# con-bot-j1-1.net
KiCad netlist of a schematic drawn in Altium Designer
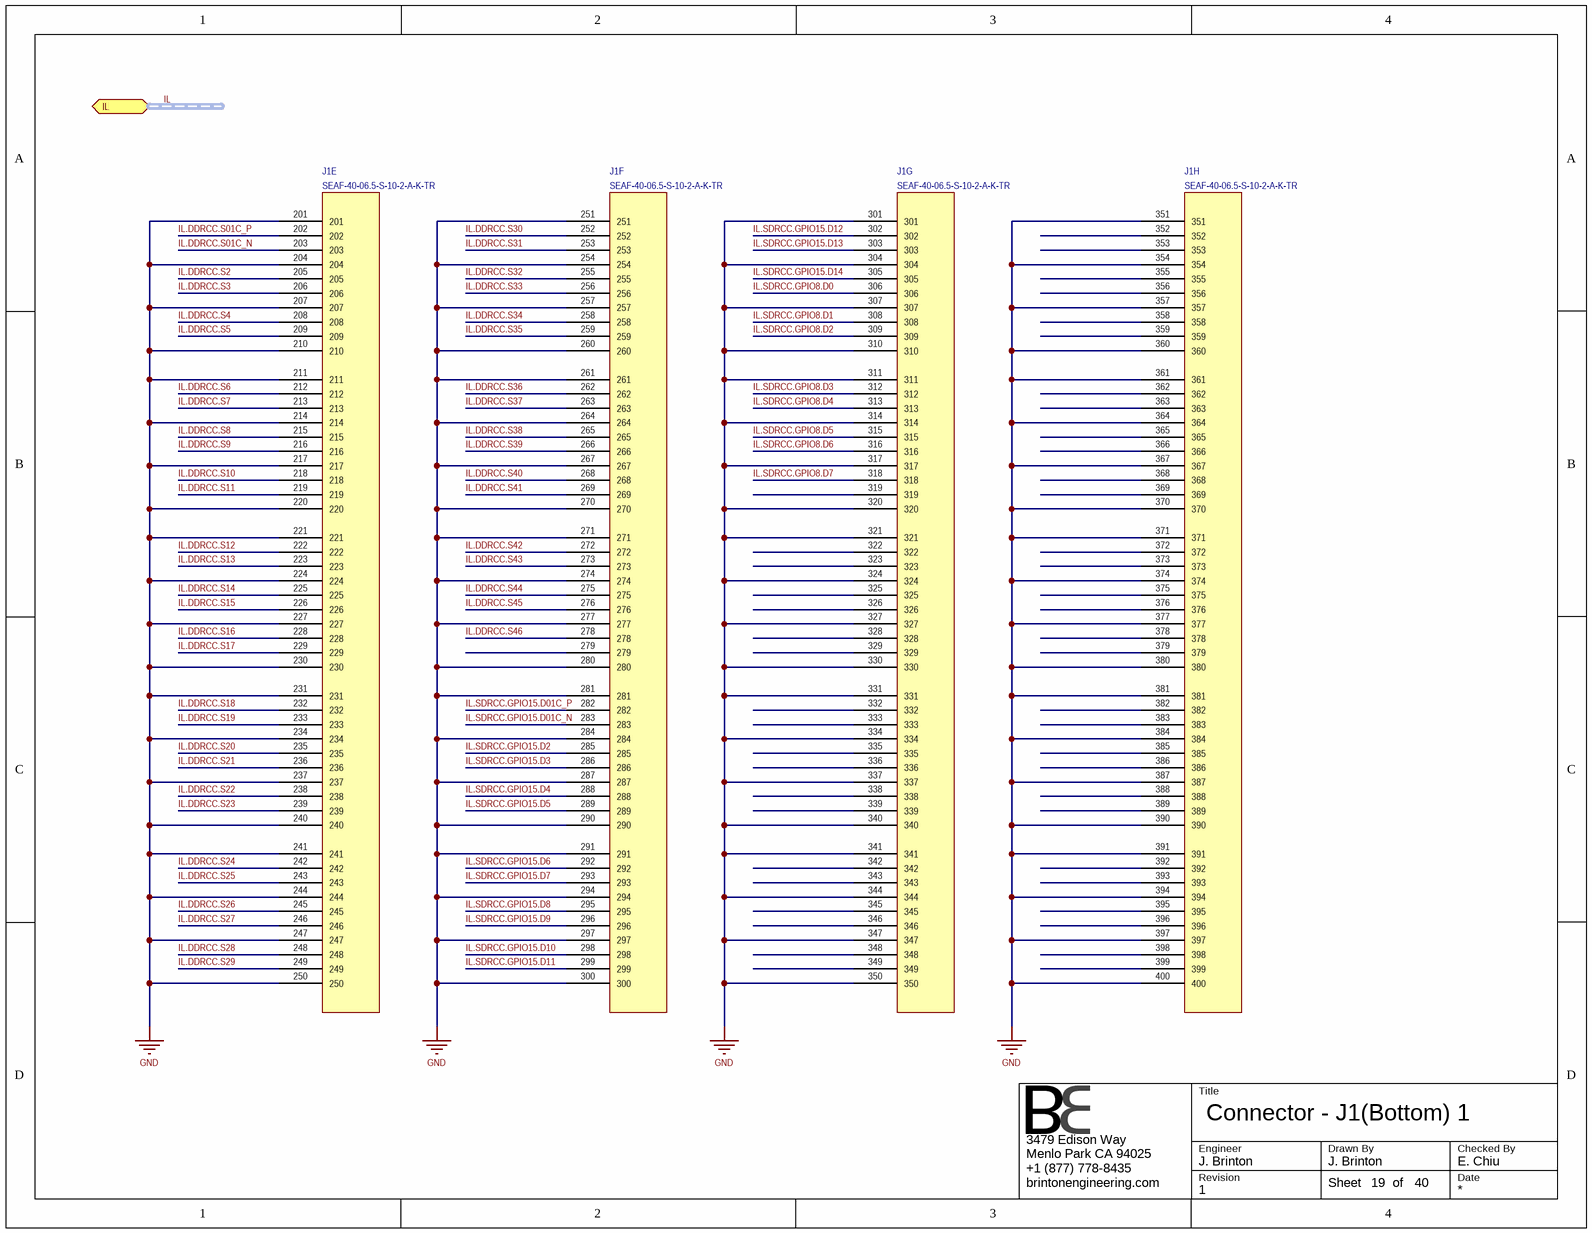
[diagram p0: con-bot-j1-1.SchDoc]

(export (version "E")
  (design (tool "Eeschema 10.0.6"))
  (components
    (comp (ref "J1")
      (value "SEAF-40-06.5-S-10-2-A-K-TR")
      (footprint "samtec:SEAF-40-06.5-S-10-2-A-K-TR")
      (description "Terminal Array Assembly, Surface Mount, 0.050\" Pitch, 400 Pins")
      (fields (field (name "MANUFACTURER") "Samtec"))
      (libsource (lib "samtec") (part "SEAF-40-06.5-S-10-2-A-K-TR"))
    )
  )
  (nets
    (net (code "2") (name "/IL.DDRCC.S01C_N") (class "Default")
      (node (ref "J1") (pin "203") (pinfunction "203_203") (pintype "passive"))
    )
    (net (code "3") (name "/IL.DDRCC.S01C_P") (class "Default")
      (node (ref "J1") (pin "202") (pinfunction "202_202") (pintype "passive"))
    )
    (net (code "4") (name "/IL.DDRCC.S2") (class "Default")
      (node (ref "J1") (pin "205") (pinfunction "205_205") (pintype "passive"))
    )
    (net (code "5") (name "/IL.DDRCC.S3") (class "Default")
      (node (ref "J1") (pin "206") (pinfunction "206_206") (pintype "passive"))
    )
    (net (code "6") (name "/IL.DDRCC.S4") (class "Default")
      (node (ref "J1") (pin "208") (pinfunction "208_208") (pintype "passive"))
    )
    (net (code "7") (name "/IL.DDRCC.S5") (class "Default")
      (node (ref "J1") (pin "209") (pinfunction "209_209") (pintype "passive"))
    )
    (net (code "8") (name "/IL.DDRCC.S6") (class "Default")
      (node (ref "J1") (pin "212") (pinfunction "212_212") (pintype "passive"))
    )
    (net (code "9") (name "/IL.DDRCC.S7") (class "Default")
      (node (ref "J1") (pin "213") (pinfunction "213_213") (pintype "passive"))
    )
    (net (code "10") (name "/IL.DDRCC.S8") (class "Default")
      (node (ref "J1") (pin "215") (pinfunction "215_215") (pintype "passive"))
    )
    (net (code "11") (name "/IL.DDRCC.S9") (class "Default")
      (node (ref "J1") (pin "216") (pinfunction "216_216") (pintype "passive"))
    )
    (net (code "12") (name "/IL.DDRCC.S10") (class "Default")
      (node (ref "J1") (pin "218") (pinfunction "218_218") (pintype "passive"))
    )
    (net (code "13") (name "/IL.DDRCC.S11") (class "Default")
      (node (ref "J1") (pin "219") (pinfunction "219_219") (pintype "passive"))
    )
    (net (code "14") (name "/IL.DDRCC.S12") (class "Default")
      (node (ref "J1") (pin "222") (pinfunction "222_222") (pintype "passive"))
    )
    (net (code "15") (name "/IL.DDRCC.S13") (class "Default")
      (node (ref "J1") (pin "223") (pinfunction "223_223") (pintype "passive"))
    )
    (net (code "16") (name "/IL.DDRCC.S14") (class "Default")
      (node (ref "J1") (pin "225") (pinfunction "225_225") (pintype "passive"))
    )
    (net (code "17") (name "/IL.DDRCC.S15") (class "Default")
      (node (ref "J1") (pin "226") (pinfunction "226_226") (pintype "passive"))
    )
    (net (code "18") (name "/IL.DDRCC.S16") (class "Default")
      (node (ref "J1") (pin "228") (pinfunction "228_228") (pintype "passive"))
    )
    (net (code "19") (name "/IL.DDRCC.S17") (class "Default")
      (node (ref "J1") (pin "229") (pinfunction "229_229") (pintype "passive"))
    )
    (net (code "20") (name "/IL.DDRCC.S18") (class "Default")
      (node (ref "J1") (pin "232") (pinfunction "232_232") (pintype "passive"))
    )
    (net (code "21") (name "/IL.DDRCC.S19") (class "Default")
      (node (ref "J1") (pin "233") (pinfunction "233_233") (pintype "passive"))
    )
    (net (code "22") (name "/IL.DDRCC.S20") (class "Default")
      (node (ref "J1") (pin "235") (pinfunction "235_235") (pintype "passive"))
    )
    (net (code "23") (name "/IL.DDRCC.S21") (class "Default")
      (node (ref "J1") (pin "236") (pinfunction "236_236") (pintype "passive"))
    )
    (net (code "24") (name "/IL.DDRCC.S22") (class "Default")
      (node (ref "J1") (pin "238") (pinfunction "238_238") (pintype "passive"))
    )
    (net (code "25") (name "/IL.DDRCC.S23") (class "Default")
      (node (ref "J1") (pin "239") (pinfunction "239_239") (pintype "passive"))
    )
    (net (code "26") (name "/IL.DDRCC.S24") (class "Default")
      (node (ref "J1") (pin "242") (pinfunction "242_242") (pintype "passive"))
    )
    (net (code "27") (name "/IL.DDRCC.S25") (class "Default")
      (node (ref "J1") (pin "243") (pinfunction "243_243") (pintype "passive"))
    )
    (net (code "28") (name "/IL.DDRCC.S26") (class "Default")
      (node (ref "J1") (pin "245") (pinfunction "245_245") (pintype "passive"))
    )
    (net (code "29") (name "/IL.DDRCC.S27") (class "Default")
      (node (ref "J1") (pin "246") (pinfunction "246_246") (pintype "passive"))
    )
    (net (code "30") (name "/IL.DDRCC.S28") (class "Default")
      (node (ref "J1") (pin "248") (pinfunction "248_248") (pintype "passive"))
    )
    (net (code "31") (name "/IL.DDRCC.S29") (class "Default")
      (node (ref "J1") (pin "249") (pinfunction "249_249") (pintype "passive"))
    )
    (net (code "32") (name "/IL.DDRCC.S30") (class "Default")
      (node (ref "J1") (pin "252") (pinfunction "252_252") (pintype "passive"))
    )
    (net (code "33") (name "/IL.DDRCC.S31") (class "Default")
      (node (ref "J1") (pin "253") (pinfunction "253_253") (pintype "passive"))
    )
    (net (code "34") (name "/IL.DDRCC.S32") (class "Default")
      (node (ref "J1") (pin "255") (pinfunction "255_255") (pintype "passive"))
    )
    (net (code "35") (name "/IL.DDRCC.S33") (class "Default")
      (node (ref "J1") (pin "256") (pinfunction "256_256") (pintype "passive"))
    )
    (net (code "36") (name "/IL.DDRCC.S34") (class "Default")
      (node (ref "J1") (pin "258") (pinfunction "258_258") (pintype "passive"))
    )
    (net (code "37") (name "/IL.DDRCC.S35") (class "Default")
      (node (ref "J1") (pin "259") (pinfunction "259_259") (pintype "passive"))
    )
    (net (code "38") (name "/IL.DDRCC.S36") (class "Default")
      (node (ref "J1") (pin "262") (pinfunction "262_262") (pintype "passive"))
    )
    (net (code "39") (name "/IL.DDRCC.S37") (class "Default")
      (node (ref "J1") (pin "263") (pinfunction "263_263") (pintype "passive"))
    )
    (net (code "40") (name "/IL.DDRCC.S38") (class "Default")
      (node (ref "J1") (pin "265") (pinfunction "265_265") (pintype "passive"))
    )
    (net (code "41") (name "/IL.DDRCC.S39") (class "Default")
      (node (ref "J1") (pin "266") (pinfunction "266_266") (pintype "passive"))
    )
    (net (code "42") (name "/IL.DDRCC.S40") (class "Default")
      (node (ref "J1") (pin "268") (pinfunction "268_268") (pintype "passive"))
    )
    (net (code "43") (name "/IL.DDRCC.S41") (class "Default")
      (node (ref "J1") (pin "269") (pinfunction "269_269") (pintype "passive"))
    )
    (net (code "44") (name "/IL.DDRCC.S42") (class "Default")
      (node (ref "J1") (pin "272") (pinfunction "272_272") (pintype "passive"))
    )
    (net (code "45") (name "/IL.DDRCC.S43") (class "Default")
      (node (ref "J1") (pin "273") (pinfunction "273_273") (pintype "passive"))
    )
    (net (code "46") (name "/IL.DDRCC.S44") (class "Default")
      (node (ref "J1") (pin "275") (pinfunction "275_275") (pintype "passive"))
    )
    (net (code "47") (name "/IL.DDRCC.S45") (class "Default")
      (node (ref "J1") (pin "276") (pinfunction "276_276") (pintype "passive"))
    )
    (net (code "48") (name "/IL.DDRCC.S46") (class "Default")
      (node (ref "J1") (pin "278") (pinfunction "278_278") (pintype "passive"))
    )
    (net (code "49") (name "/IL.SDRCC.GPIO8.D0") (class "Default")
      (node (ref "J1") (pin "306") (pinfunction "306_306") (pintype "passive"))
    )
    (net (code "50") (name "/IL.SDRCC.GPIO8.D1") (class "Default")
      (node (ref "J1") (pin "308") (pinfunction "308_308") (pintype "passive"))
    )
    (net (code "51") (name "/IL.SDRCC.GPIO8.D2") (class "Default")
      (node (ref "J1") (pin "309") (pinfunction "309_309") (pintype "passive"))
    )
    (net (code "52") (name "/IL.SDRCC.GPIO8.D3") (class "Default")
      (node (ref "J1") (pin "312") (pinfunction "312_312") (pintype "passive"))
    )
    (net (code "53") (name "/IL.SDRCC.GPIO8.D4") (class "Default")
      (node (ref "J1") (pin "313") (pinfunction "313_313") (pintype "passive"))
    )
    (net (code "54") (name "/IL.SDRCC.GPIO8.D5") (class "Default")
      (node (ref "J1") (pin "315") (pinfunction "315_315") (pintype "passive"))
    )
    (net (code "55") (name "/IL.SDRCC.GPIO8.D6") (class "Default")
      (node (ref "J1") (pin "316") (pinfunction "316_316") (pintype "passive"))
    )
    (net (code "56") (name "/IL.SDRCC.GPIO8.D7") (class "Default")
      (node (ref "J1") (pin "318") (pinfunction "318_318") (pintype "passive"))
    )
    (net (code "57") (name "/IL.SDRCC.GPIO15.D01C_N") (class "Default")
      (node (ref "J1") (pin "283") (pinfunction "283_283") (pintype "passive"))
    )
    (net (code "58") (name "/IL.SDRCC.GPIO15.D01C_P") (class "Default")
      (node (ref "J1") (pin "282") (pinfunction "282_282") (pintype "passive"))
    )
    (net (code "59") (name "/IL.SDRCC.GPIO15.D2") (class "Default")
      (node (ref "J1") (pin "285") (pinfunction "285_285") (pintype "passive"))
    )
    (net (code "60") (name "/IL.SDRCC.GPIO15.D3") (class "Default")
      (node (ref "J1") (pin "286") (pinfunction "286_286") (pintype "passive"))
    )
    (net (code "61") (name "/IL.SDRCC.GPIO15.D4") (class "Default")
      (node (ref "J1") (pin "288") (pinfunction "288_288") (pintype "passive"))
    )
    (net (code "62") (name "/IL.SDRCC.GPIO15.D5") (class "Default")
      (node (ref "J1") (pin "289") (pinfunction "289_289") (pintype "passive"))
    )
    (net (code "63") (name "/IL.SDRCC.GPIO15.D6") (class "Default")
      (node (ref "J1") (pin "292") (pinfunction "292_292") (pintype "passive"))
    )
    (net (code "64") (name "/IL.SDRCC.GPIO15.D7") (class "Default")
      (node (ref "J1") (pin "293") (pinfunction "293_293") (pintype "passive"))
    )
    (net (code "65") (name "/IL.SDRCC.GPIO15.D8") (class "Default")
      (node (ref "J1") (pin "295") (pinfunction "295_295") (pintype "passive"))
    )
    (net (code "66") (name "/IL.SDRCC.GPIO15.D9") (class "Default")
      (node (ref "J1") (pin "296") (pinfunction "296_296") (pintype "passive"))
    )
    (net (code "67") (name "/IL.SDRCC.GPIO15.D10") (class "Default")
      (node (ref "J1") (pin "298") (pinfunction "298_298") (pintype "passive"))
    )
    (net (code "68") (name "/IL.SDRCC.GPIO15.D11") (class "Default")
      (node (ref "J1") (pin "299") (pinfunction "299_299") (pintype "passive"))
    )
    (net (code "69") (name "/IL.SDRCC.GPIO15.D12") (class "Default")
      (node (ref "J1") (pin "302") (pinfunction "302_302") (pintype "passive"))
    )
    (net (code "70") (name "/IL.SDRCC.GPIO15.D13") (class "Default")
      (node (ref "J1") (pin "303") (pinfunction "303_303") (pintype "passive"))
    )
    (net (code "71") (name "/IL.SDRCC.GPIO15.D14") (class "Default")
      (node (ref "J1") (pin "305") (pinfunction "305_305") (pintype "passive"))
    )
    (net (code "73") (name "GND") (class "Default")
      (node (ref "J1") (pin "201") (pinfunction "201_201") (pintype "passive"))
      (node (ref "J1") (pin "204") (pinfunction "204_204") (pintype "passive"))
      (node (ref "J1") (pin "207") (pinfunction "207_207") (pintype "passive"))
      (node (ref "J1") (pin "210") (pinfunction "210_210") (pintype "passive"))
      (node (ref "J1") (pin "211") (pinfunction "211_211") (pintype "passive"))
      (node (ref "J1") (pin "214") (pinfunction "214_214") (pintype "passive"))
      (node (ref "J1") (pin "217") (pinfunction "217_217") (pintype "passive"))
      (node (ref "J1") (pin "220") (pinfunction "220_220") (pintype "passive"))
      (node (ref "J1") (pin "221") (pinfunction "221_221") (pintype "passive"))
      (node (ref "J1") (pin "224") (pinfunction "224_224") (pintype "passive"))
      (node (ref "J1") (pin "227") (pinfunction "227_227") (pintype "passive"))
      (node (ref "J1") (pin "230") (pinfunction "230_230") (pintype "passive"))
      (node (ref "J1") (pin "231") (pinfunction "231_231") (pintype "passive"))
      (node (ref "J1") (pin "234") (pinfunction "234_234") (pintype "passive"))
      (node (ref "J1") (pin "237") (pinfunction "237_237") (pintype "passive"))
      (node (ref "J1") (pin "240") (pinfunction "240_240") (pintype "passive"))
      (node (ref "J1") (pin "241") (pinfunction "241_241") (pintype "passive"))
      (node (ref "J1") (pin "244") (pinfunction "244_244") (pintype "passive"))
      (node (ref "J1") (pin "247") (pinfunction "247_247") (pintype "passive"))
      (node (ref "J1") (pin "250") (pinfunction "250_250") (pintype "passive"))
      (node (ref "J1") (pin "251") (pinfunction "251_251") (pintype "passive"))
      (node (ref "J1") (pin "254") (pinfunction "254_254") (pintype "passive"))
      (node (ref "J1") (pin "257") (pinfunction "257_257") (pintype "passive"))
      (node (ref "J1") (pin "260") (pinfunction "260_260") (pintype "passive"))
      (node (ref "J1") (pin "261") (pinfunction "261_261") (pintype "passive"))
      (node (ref "J1") (pin "264") (pinfunction "264_264") (pintype "passive"))
      (node (ref "J1") (pin "267") (pinfunction "267_267") (pintype "passive"))
      (node (ref "J1") (pin "270") (pinfunction "270_270") (pintype "passive"))
      (node (ref "J1") (pin "271") (pinfunction "271_271") (pintype "passive"))
      (node (ref "J1") (pin "274") (pinfunction "274_274") (pintype "passive"))
      (node (ref "J1") (pin "277") (pinfunction "277_277") (pintype "passive"))
      (node (ref "J1") (pin "280") (pinfunction "280_280") (pintype "passive"))
      (node (ref "J1") (pin "281") (pinfunction "281_281") (pintype "passive"))
      (node (ref "J1") (pin "284") (pinfunction "284_284") (pintype "passive"))
      (node (ref "J1") (pin "287") (pinfunction "287_287") (pintype "passive"))
      (node (ref "J1") (pin "290") (pinfunction "290_290") (pintype "passive"))
      (node (ref "J1") (pin "291") (pinfunction "291_291") (pintype "passive"))
      (node (ref "J1") (pin "294") (pinfunction "294_294") (pintype "passive"))
      (node (ref "J1") (pin "297") (pinfunction "297_297") (pintype "passive"))
      (node (ref "J1") (pin "300") (pinfunction "300_300") (pintype "passive"))
      (node (ref "J1") (pin "301") (pinfunction "301_301") (pintype "passive"))
      (node (ref "J1") (pin "304") (pinfunction "304_304") (pintype "passive"))
      (node (ref "J1") (pin "307") (pinfunction "307_307") (pintype "passive"))
      (node (ref "J1") (pin "310") (pinfunction "310_310") (pintype "passive"))
      (node (ref "J1") (pin "311") (pinfunction "311_311") (pintype "passive"))
      (node (ref "J1") (pin "314") (pinfunction "314_314") (pintype "passive"))
      (node (ref "J1") (pin "317") (pinfunction "317_317") (pintype "passive"))
      (node (ref "J1") (pin "320") (pinfunction "320_320") (pintype "passive"))
      (node (ref "J1") (pin "321") (pinfunction "321_321") (pintype "passive"))
      (node (ref "J1") (pin "324") (pinfunction "324_324") (pintype "passive"))
      (node (ref "J1") (pin "327") (pinfunction "327_327") (pintype "passive"))
      (node (ref "J1") (pin "330") (pinfunction "330_330") (pintype "passive"))
      (node (ref "J1") (pin "331") (pinfunction "331_331") (pintype "passive"))
      (node (ref "J1") (pin "334") (pinfunction "334_334") (pintype "passive"))
      (node (ref "J1") (pin "337") (pinfunction "337_337") (pintype "passive"))
      (node (ref "J1") (pin "340") (pinfunction "340_340") (pintype "passive"))
      (node (ref "J1") (pin "341") (pinfunction "341_341") (pintype "passive"))
      (node (ref "J1") (pin "344") (pinfunction "344_344") (pintype "passive"))
      (node (ref "J1") (pin "347") (pinfunction "347_347") (pintype "passive"))
      (node (ref "J1") (pin "350") (pinfunction "350_350") (pintype "passive"))
      (node (ref "J1") (pin "351") (pinfunction "351_351") (pintype "passive"))
      (node (ref "J1") (pin "354") (pinfunction "354_354") (pintype "passive"))
      (node (ref "J1") (pin "357") (pinfunction "357_357") (pintype "passive"))
      (node (ref "J1") (pin "360") (pinfunction "360_360") (pintype "passive"))
      (node (ref "J1") (pin "361") (pinfunction "361_361") (pintype "passive"))
      (node (ref "J1") (pin "364") (pinfunction "364_364") (pintype "passive"))
      (node (ref "J1") (pin "367") (pinfunction "367_367") (pintype "passive"))
      (node (ref "J1") (pin "370") (pinfunction "370_370") (pintype "passive"))
      (node (ref "J1") (pin "371") (pinfunction "371_371") (pintype "passive"))
      (node (ref "J1") (pin "374") (pinfunction "374_374") (pintype "passive"))
      (node (ref "J1") (pin "377") (pinfunction "377_377") (pintype "passive"))
      (node (ref "J1") (pin "380") (pinfunction "380_380") (pintype "passive"))
      (node (ref "J1") (pin "381") (pinfunction "381_381") (pintype "passive"))
      (node (ref "J1") (pin "384") (pinfunction "384_384") (pintype "passive"))
      (node (ref "J1") (pin "387") (pinfunction "387_387") (pintype "passive"))
      (node (ref "J1") (pin "390") (pinfunction "390_390") (pintype "passive"))
      (node (ref "J1") (pin "391") (pinfunction "391_391") (pintype "passive"))
      (node (ref "J1") (pin "394") (pinfunction "394_394") (pintype "passive"))
      (node (ref "J1") (pin "397") (pinfunction "397_397") (pintype "passive"))
      (node (ref "J1") (pin "400") (pinfunction "400_400") (pintype "passive"))
    )
    (net (code "74") (name "unconnected-(J1-Pad279)") (class "Default")
      (node (ref "J1") (pin "279") (pinfunction "279_279") (pintype "passive"))
    )
    (net (code "75") (name "unconnected-(J1-Pad319)") (class "Default")
      (node (ref "J1") (pin "319") (pinfunction "319_319") (pintype "passive"))
    )
    (net (code "76") (name "unconnected-(J1-Pad322)") (class "Default")
      (node (ref "J1") (pin "322") (pinfunction "322_322") (pintype "passive"))
    )
    (net (code "77") (name "unconnected-(J1-Pad323)") (class "Default")
      (node (ref "J1") (pin "323") (pinfunction "323_323") (pintype "passive"))
    )
    (net (code "78") (name "unconnected-(J1-Pad325)") (class "Default")
      (node (ref "J1") (pin "325") (pinfunction "325_325") (pintype "passive"))
    )
    (net (code "79") (name "unconnected-(J1-Pad326)") (class "Default")
      (node (ref "J1") (pin "326") (pinfunction "326_326") (pintype "passive"))
    )
    (net (code "80") (name "unconnected-(J1-Pad328)") (class "Default")
      (node (ref "J1") (pin "328") (pinfunction "328_328") (pintype "passive"))
    )
    (net (code "81") (name "unconnected-(J1-Pad329)") (class "Default")
      (node (ref "J1") (pin "329") (pinfunction "329_329") (pintype "passive"))
    )
    (net (code "82") (name "unconnected-(J1-Pad332)") (class "Default")
      (node (ref "J1") (pin "332") (pinfunction "332_332") (pintype "passive"))
    )
    (net (code "83") (name "unconnected-(J1-Pad333)") (class "Default")
      (node (ref "J1") (pin "333") (pinfunction "333_333") (pintype "passive"))
    )
    (net (code "84") (name "unconnected-(J1-Pad335)") (class "Default")
      (node (ref "J1") (pin "335") (pinfunction "335_335") (pintype "passive"))
    )
    (net (code "85") (name "unconnected-(J1-Pad336)") (class "Default")
      (node (ref "J1") (pin "336") (pinfunction "336_336") (pintype "passive"))
    )
    (net (code "86") (name "unconnected-(J1-Pad338)") (class "Default")
      (node (ref "J1") (pin "338") (pinfunction "338_338") (pintype "passive"))
    )
    (net (code "87") (name "unconnected-(J1-Pad339)") (class "Default")
      (node (ref "J1") (pin "339") (pinfunction "339_339") (pintype "passive"))
    )
    (net (code "88") (name "unconnected-(J1-Pad342)") (class "Default")
      (node (ref "J1") (pin "342") (pinfunction "342_342") (pintype "passive"))
    )
    (net (code "89") (name "unconnected-(J1-Pad343)") (class "Default")
      (node (ref "J1") (pin "343") (pinfunction "343_343") (pintype "passive"))
    )
    (net (code "90") (name "unconnected-(J1-Pad345)") (class "Default")
      (node (ref "J1") (pin "345") (pinfunction "345_345") (pintype "passive"))
    )
    (net (code "91") (name "unconnected-(J1-Pad346)") (class "Default")
      (node (ref "J1") (pin "346") (pinfunction "346_346") (pintype "passive"))
    )
    (net (code "92") (name "unconnected-(J1-Pad348)") (class "Default")
      (node (ref "J1") (pin "348") (pinfunction "348_348") (pintype "passive"))
    )
    (net (code "93") (name "unconnected-(J1-Pad349)") (class "Default")
      (node (ref "J1") (pin "349") (pinfunction "349_349") (pintype "passive"))
    )
    (net (code "94") (name "unconnected-(J1-Pad352)") (class "Default")
      (node (ref "J1") (pin "352") (pinfunction "352_352") (pintype "passive"))
    )
    (net (code "95") (name "unconnected-(J1-Pad353)") (class "Default")
      (node (ref "J1") (pin "353") (pinfunction "353_353") (pintype "passive"))
    )
    (net (code "96") (name "unconnected-(J1-Pad355)") (class "Default")
      (node (ref "J1") (pin "355") (pinfunction "355_355") (pintype "passive"))
    )
    (net (code "97") (name "unconnected-(J1-Pad356)") (class "Default")
      (node (ref "J1") (pin "356") (pinfunction "356_356") (pintype "passive"))
    )
    (net (code "98") (name "unconnected-(J1-Pad358)") (class "Default")
      (node (ref "J1") (pin "358") (pinfunction "358_358") (pintype "passive"))
    )
    (net (code "99") (name "unconnected-(J1-Pad359)") (class "Default")
      (node (ref "J1") (pin "359") (pinfunction "359_359") (pintype "passive"))
    )
    (net (code "100") (name "unconnected-(J1-Pad362)") (class "Default")
      (node (ref "J1") (pin "362") (pinfunction "362_362") (pintype "passive"))
    )
    (net (code "101") (name "unconnected-(J1-Pad363)") (class "Default")
      (node (ref "J1") (pin "363") (pinfunction "363_363") (pintype "passive"))
    )
    (net (code "102") (name "unconnected-(J1-Pad365)") (class "Default")
      (node (ref "J1") (pin "365") (pinfunction "365_365") (pintype "passive"))
    )
    (net (code "103") (name "unconnected-(J1-Pad366)") (class "Default")
      (node (ref "J1") (pin "366") (pinfunction "366_366") (pintype "passive"))
    )
    (net (code "104") (name "unconnected-(J1-Pad368)") (class "Default")
      (node (ref "J1") (pin "368") (pinfunction "368_368") (pintype "passive"))
    )
    (net (code "105") (name "unconnected-(J1-Pad369)") (class "Default")
      (node (ref "J1") (pin "369") (pinfunction "369_369") (pintype "passive"))
    )
    (net (code "106") (name "unconnected-(J1-Pad372)") (class "Default")
      (node (ref "J1") (pin "372") (pinfunction "372_372") (pintype "passive"))
    )
    (net (code "107") (name "unconnected-(J1-Pad373)") (class "Default")
      (node (ref "J1") (pin "373") (pinfunction "373_373") (pintype "passive"))
    )
    (net (code "108") (name "unconnected-(J1-Pad375)") (class "Default")
      (node (ref "J1") (pin "375") (pinfunction "375_375") (pintype "passive"))
    )
    (net (code "109") (name "unconnected-(J1-Pad376)") (class "Default")
      (node (ref "J1") (pin "376") (pinfunction "376_376") (pintype "passive"))
    )
    (net (code "110") (name "unconnected-(J1-Pad378)") (class "Default")
      (node (ref "J1") (pin "378") (pinfunction "378_378") (pintype "passive"))
    )
    (net (code "111") (name "unconnected-(J1-Pad379)") (class "Default")
      (node (ref "J1") (pin "379") (pinfunction "379_379") (pintype "passive"))
    )
    (net (code "112") (name "unconnected-(J1-Pad382)") (class "Default")
      (node (ref "J1") (pin "382") (pinfunction "382_382") (pintype "passive"))
    )
    (net (code "113") (name "unconnected-(J1-Pad383)") (class "Default")
      (node (ref "J1") (pin "383") (pinfunction "383_383") (pintype "passive"))
    )
    (net (code "114") (name "unconnected-(J1-Pad385)") (class "Default")
      (node (ref "J1") (pin "385") (pinfunction "385_385") (pintype "passive"))
    )
    (net (code "115") (name "unconnected-(J1-Pad386)") (class "Default")
      (node (ref "J1") (pin "386") (pinfunction "386_386") (pintype "passive"))
    )
    (net (code "116") (name "unconnected-(J1-Pad388)") (class "Default")
      (node (ref "J1") (pin "388") (pinfunction "388_388") (pintype "passive"))
    )
    (net (code "117") (name "unconnected-(J1-Pad389)") (class "Default")
      (node (ref "J1") (pin "389") (pinfunction "389_389") (pintype "passive"))
    )
    (net (code "118") (name "unconnected-(J1-Pad392)") (class "Default")
      (node (ref "J1") (pin "392") (pinfunction "392_392") (pintype "passive"))
    )
    (net (code "119") (name "unconnected-(J1-Pad393)") (class "Default")
      (node (ref "J1") (pin "393") (pinfunction "393_393") (pintype "passive"))
    )
    (net (code "120") (name "unconnected-(J1-Pad395)") (class "Default")
      (node (ref "J1") (pin "395") (pinfunction "395_395") (pintype "passive"))
    )
    (net (code "121") (name "unconnected-(J1-Pad396)") (class "Default")
      (node (ref "J1") (pin "396") (pinfunction "396_396") (pintype "passive"))
    )
    (net (code "122") (name "unconnected-(J1-Pad398)") (class "Default")
      (node (ref "J1") (pin "398") (pinfunction "398_398") (pintype "passive"))
    )
    (net (code "123") (name "unconnected-(J1-Pad399)") (class "Default")
      (node (ref "J1") (pin "399") (pinfunction "399_399") (pintype "passive"))
    )
  )
)
